# POWER_MEASUREMENT.net
KiCad netlist of a schematic drawn in Altium Designer
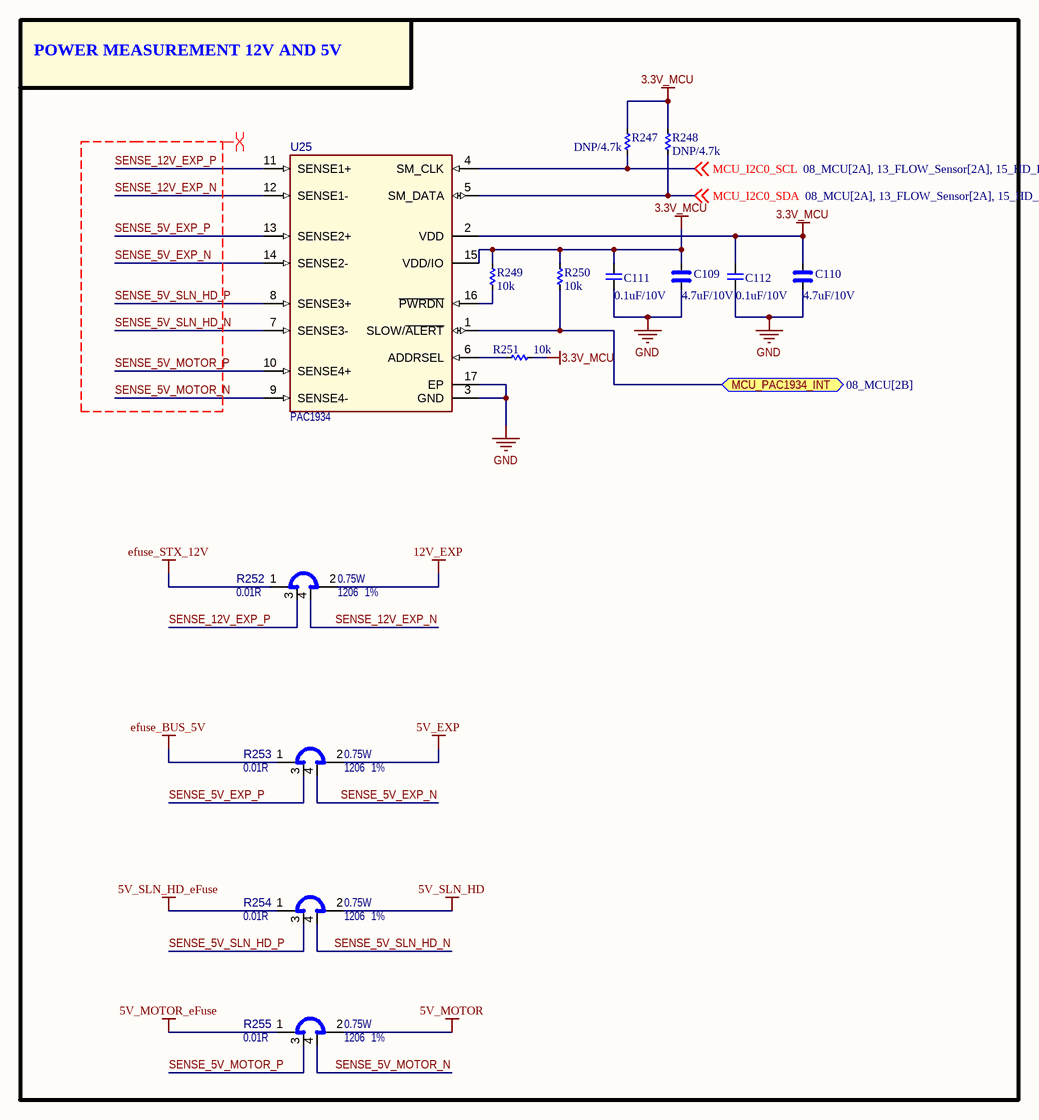
[diagram p0: POWER_MEASUREMENT.SchDoc]

(export (version "E")
  (design (tool "Eeschema 10.0.6"))
  (components
    (comp (ref "C109")
      (value "4.7uF/10V")
      (footprint "CAP_C_1005X50_L")
      (description "CAP")
      (libsource (lib "LABLIB") (part "_CAP_C_High_2"))
    )
    (comp (ref "C110")
      (value "4.7uF/10V")
      (footprint "CAP_C_1005X50_L")
      (description "CAP")
      (libsource (lib "LABLIB") (part "_CAP_C_High_2"))
    )
    (comp (ref "C111")
      (value "0.1uF/10V")
      (footprint "CAP_C_1005X50_L")
      (description "CAP")
      (libsource (lib "LABLIB") (part "_CAP_C_2"))
    )
    (comp (ref "C112")
      (value "0.1uF/10V")
      (footprint "CAP_C_1005X50_L")
      (description "CAP")
      (libsource (lib "LABLIB") (part "_CAP_C_2"))
    )
    (comp (ref "R247")
      (value "DNP/4.7k")
      (footprint "RES_C_1005x30_L")
      (description "RES")
      (libsource (lib "LABLIB") (part "_RES_B_2"))
    )
    (comp (ref "R248")
      (value "DNP/4.7k")
      (footprint "RES_C_1005x30_L")
      (description "RES")
      (libsource (lib "LABLIB") (part "_RES_B_2"))
    )
    (comp (ref "R249")
      (value "10k")
      (footprint "RES_C_1005x30_L")
      (description "RES")
      (libsource (lib "LABLIB") (part "_RES_B_2"))
    )
    (comp (ref "R250")
      (value "10k")
      (footprint "RES_C_1005x30_L")
      (description "RES")
      (libsource (lib "LABLIB") (part "_RES_B_2"))
    )
    (comp (ref "R251")
      (value "10k")
      (footprint "RES_C_1005x30_L")
      (description "RES")
      (libsource (lib "LABLIB") (part "_RES_B_2"))
    )
    (comp (ref "R252")
      (value "0.01R")
      (footprint "RES_C_1206_SHUNT")
      (description "Shunt")
      (fields
        (field (name "PACKAGE") "1206")
        (field (name "TOLERANCE") "1%")
        (field (name "POWER") "0.75W")
        (field (name "Comment") "KRL1632E-M-R010-F-T5")
        (field (name "OWNER") "Ciprian Abramov")
      )
      (libsource (lib "LABLIB") (part "Shunt 4 Pin"))
    )
    (comp (ref "R253")
      (value "0.01R")
      (footprint "RES_C_1206_SHUNT")
      (description "Shunt")
      (fields
        (field (name "PACKAGE") "1206")
        (field (name "TOLERANCE") "1%")
        (field (name "POWER") "0.75W")
        (field (name "Comment") "KRL1632E-M-R010-F-T5")
        (field (name "OWNER") "Ciprian Abramov")
      )
      (libsource (lib "LABLIB") (part "Shunt 4 Pin"))
    )
    (comp (ref "R254")
      (value "0.01R")
      (footprint "RES_C_1206_SHUNT")
      (description "Shunt")
      (fields
        (field (name "PACKAGE") "1206")
        (field (name "TOLERANCE") "1%")
        (field (name "POWER") "0.75W")
        (field (name "Comment") "KRL1632E-M-R010-F-T5")
        (field (name "OWNER") "Ciprian Abramov")
      )
      (libsource (lib "LABLIB") (part "Shunt 4 Pin"))
    )
    (comp (ref "R255")
      (value "0.01R")
      (footprint "RES_C_1206_SHUNT")
      (description "Shunt")
      (fields
        (field (name "PACKAGE") "1206")
        (field (name "TOLERANCE") "1%")
        (field (name "POWER") "0.75W")
        (field (name "Comment") "KRL1632E-M-R010-F-T5")
        (field (name "OWNER") "Ciprian Abramov")
      )
      (libsource (lib "LABLIB") (part "Shunt 4 Pin"))
    )
    (comp (ref "U25")
      (value "PAC1934")
      (footprint "UQFN-16_4X4_EP2.6X2.6")
      (fields (field (name "Comment") "PAC1934 UQFN-16") (field (name "OWNER") "Ciprian Abramov"))
      (libsource (lib "LABLIB") (part "PAC1934 UQFN-16"))
    )
  )
  (nets
    (net (code "1") (name "/MCU_PAC1934_INT") (class "Default")
      (node (ref "R250") (pin "2") (pinfunction "2_2") (pintype "passive"))
      (node (ref "U25") (pin "1") (pinfunction "SLOW/~{ALERT}_1") (pintype "bidirectional"))
    )
    (net (code "2") (name "/SENSE_5V_EXP_N") (class "Default")
      (node (ref "R253") (pin "4") (pinfunction "4_4") (pintype "passive"))
      (node (ref "U25") (pin "14") (pinfunction "SENSE2-_14") (pintype "input"))
    )
    (net (code "3") (name "/SENSE_5V_EXP_P") (class "Default")
      (node (ref "R253") (pin "3") (pinfunction "3_3") (pintype "passive"))
      (node (ref "U25") (pin "13") (pinfunction "SENSE2+_13") (pintype "input"))
    )
    (net (code "4") (name "/SENSE_5V_MOTOR_N") (class "Default")
      (node (ref "R255") (pin "4") (pinfunction "4_4") (pintype "passive"))
      (node (ref "U25") (pin "9") (pinfunction "SENSE4-_9") (pintype "input"))
    )
    (net (code "5") (name "/SENSE_5V_MOTOR_P") (class "Default")
      (node (ref "R255") (pin "3") (pinfunction "3_3") (pintype "passive"))
      (node (ref "U25") (pin "10") (pinfunction "SENSE4+_10") (pintype "input"))
    )
    (net (code "6") (name "/SENSE_5V_SLN_HD_N") (class "Default")
      (node (ref "R254") (pin "4") (pinfunction "4_4") (pintype "passive"))
      (node (ref "U25") (pin "7") (pinfunction "SENSE3-_7") (pintype "input"))
    )
    (net (code "7") (name "/SENSE_5V_SLN_HD_P") (class "Default")
      (node (ref "R254") (pin "3") (pinfunction "3_3") (pintype "passive"))
      (node (ref "U25") (pin "8") (pinfunction "SENSE3+_8") (pintype "input"))
    )
    (net (code "8") (name "/SENSE_12V_EXP_N") (class "Default")
      (node (ref "R252") (pin "4") (pinfunction "4_4") (pintype "passive"))
      (node (ref "U25") (pin "12") (pinfunction "SENSE1-_12") (pintype "input"))
    )
    (net (code "9") (name "/SENSE_12V_EXP_P") (class "Default")
      (node (ref "R252") (pin "3") (pinfunction "3_3") (pintype "passive"))
      (node (ref "U25") (pin "11") (pinfunction "SENSE1+_11") (pintype "input"))
    )
    (net (code "10") (name "3.3V_MCU") (class "Default")
      (node (ref "C109") (pin "1") (pinfunction "1_1") (pintype "passive"))
      (node (ref "C110") (pin "1") (pinfunction "1_1") (pintype "passive"))
      (node (ref "C111") (pin "1") (pinfunction "1_1") (pintype "passive"))
      (node (ref "C112") (pin "1") (pinfunction "1_1") (pintype "passive"))
      (node (ref "R247") (pin "1") (pinfunction "1_1") (pintype "passive"))
      (node (ref "R248") (pin "1") (pinfunction "1_1") (pintype "passive"))
      (node (ref "R249") (pin "1") (pinfunction "1_1") (pintype "passive"))
      (node (ref "R250") (pin "1") (pinfunction "1_1") (pintype "passive"))
      (node (ref "R251") (pin "2") (pinfunction "2_2") (pintype "passive"))
      (node (ref "U25") (pin "15") (pinfunction "VDD/IO_15") (pintype "power_in"))
      (node (ref "U25") (pin "2") (pinfunction "VDD_2") (pintype "power_in"))
    )
    (net (code "11") (name "5V_EXP") (class "Default")
      (node (ref "R253") (pin "2") (pinfunction "2_2") (pintype "passive"))
    )
    (net (code "12") (name "5V_MOTOR") (class "Default")
      (node (ref "R255") (pin "2") (pinfunction "2_2") (pintype "passive"))
    )
    (net (code "13") (name "5V_MOTOR_eFuse") (class "Default")
      (node (ref "R255") (pin "1") (pinfunction "1_1") (pintype "passive"))
    )
    (net (code "14") (name "5V_SLN_HD") (class "Default")
      (node (ref "R254") (pin "2") (pinfunction "2_2") (pintype "passive"))
    )
    (net (code "15") (name "5V_SLN_HD_eFuse") (class "Default")
      (node (ref "R254") (pin "1") (pinfunction "1_1") (pintype "passive"))
    )
    (net (code "16") (name "12V_EXP") (class "Default")
      (node (ref "R252") (pin "2") (pinfunction "2_2") (pintype "passive"))
    )
    (net (code "17") (name "GND") (class "Default")
      (node (ref "C109") (pin "2") (pinfunction "2_2") (pintype "passive"))
      (node (ref "C110") (pin "2") (pinfunction "2_2") (pintype "passive"))
      (node (ref "C111") (pin "2") (pinfunction "2_2") (pintype "passive"))
      (node (ref "C112") (pin "2") (pinfunction "2_2") (pintype "passive"))
      (node (ref "U25") (pin "17") (pinfunction "EP_17") (pintype "passive"))
      (node (ref "U25") (pin "3") (pinfunction "GND_3") (pintype "power_in"))
    )
    (net (code "18") (name "MCU_I2C0_SCL") (class "Default")
      (node (ref "R247") (pin "2") (pinfunction "2_2") (pintype "passive"))
      (node (ref "U25") (pin "4") (pinfunction "SM_CLK_4") (pintype "input"))
    )
    (net (code "19") (name "MCU_I2C0_SDA") (class "Default")
      (node (ref "R248") (pin "2") (pinfunction "2_2") (pintype "passive"))
      (node (ref "U25") (pin "5") (pinfunction "SM_DATA_5") (pintype "bidirectional"))
    )
    (net (code "20") (name "Net-(U25-ADDRSEL)") (class "Default")
      (node (ref "R251") (pin "1") (pinfunction "1_1") (pintype "passive"))
      (node (ref "U25") (pin "6") (pinfunction "ADDRSEL_6") (pintype "input"))
    )
    (net (code "21") (name "Net-(U25-~{PWRDN})") (class "Default")
      (node (ref "R249") (pin "2") (pinfunction "2_2") (pintype "passive"))
      (node (ref "U25") (pin "16") (pinfunction "~{PWRDN}_16") (pintype "input"))
    )
    (net (code "22") (name "efuse_BUS_5V") (class "Default")
      (node (ref "R253") (pin "1") (pinfunction "1_1") (pintype "passive"))
    )
    (net (code "23") (name "efuse_STX_12V") (class "Default")
      (node (ref "R252") (pin "1") (pinfunction "1_1") (pintype "passive"))
    )
  )
)
